# thermocouple_reader.net
KiCad netlist of a schematic drawn in EAGLE
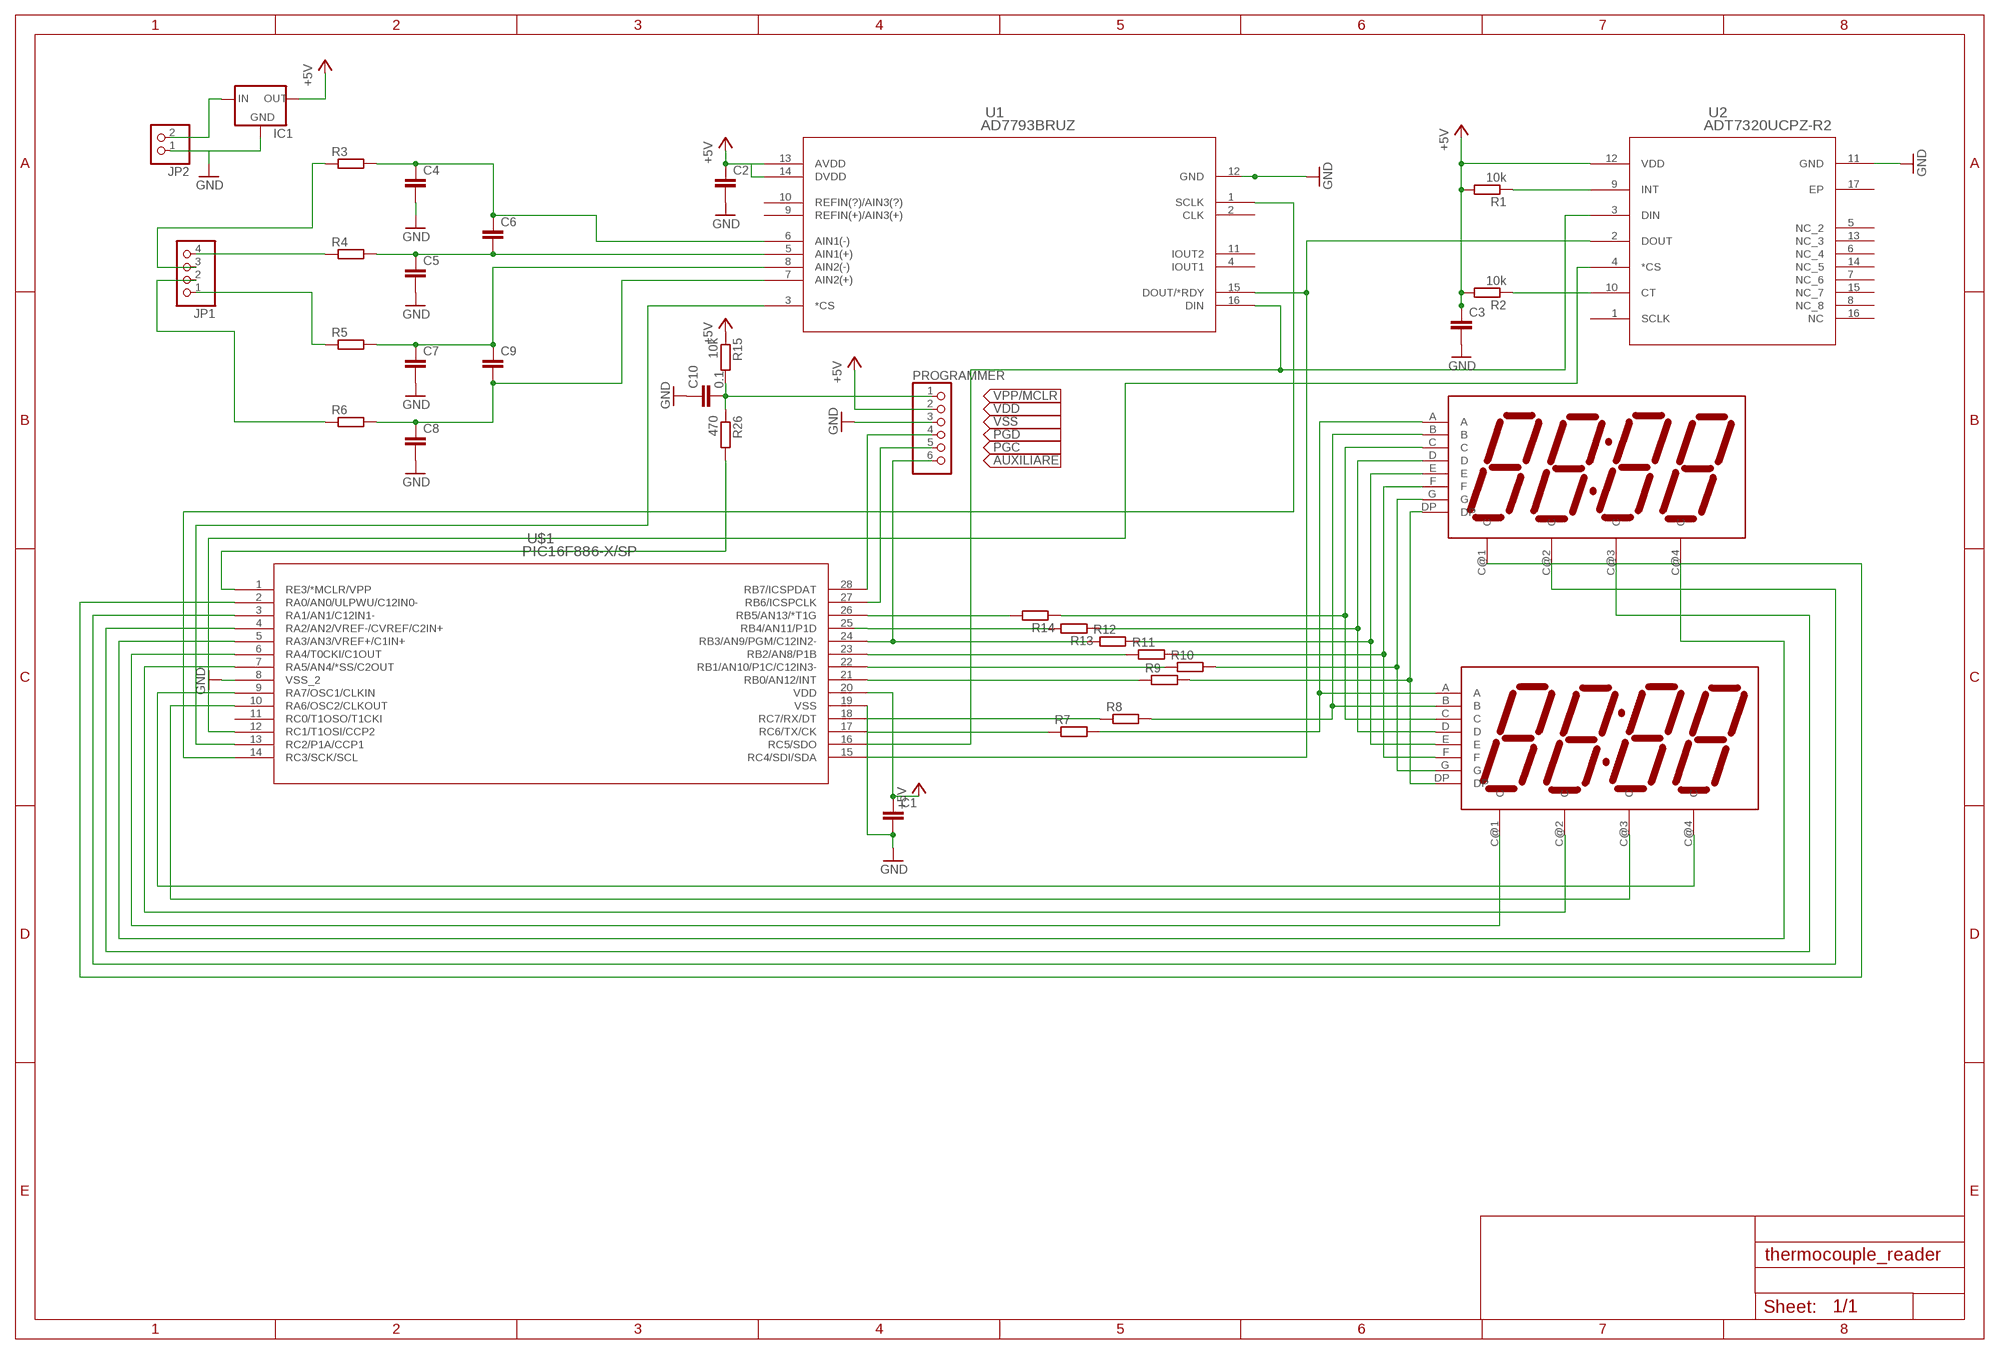
[diagram p0: schematic, sheet 1]

(export (version "E")
  (design (tool "Eeschema 10.0.6"))
  (components
    (comp (ref "C1")
      (value "C-EU025-024X044")
      (footprint "eagle-import:C025-024X044")
      (libsource (lib "eagle-import") (part "C-EU025-024X044"))
    )
    (comp (ref "C2")
      (value "C-EU025-024X044")
      (footprint "eagle-import:C025-024X044")
      (libsource (lib "eagle-import") (part "C-EU025-024X044"))
    )
    (comp (ref "C3")
      (value "C-EU025-024X044")
      (footprint "eagle-import:C025-024X044")
      (libsource (lib "eagle-import") (part "C-EU025-024X044"))
    )
    (comp (ref "C4")
      (value "C-EU025-025X050")
      (footprint "eagle-import:C025-025X050")
      (libsource (lib "eagle-import") (part "C-EU025-025X050"))
    )
    (comp (ref "C5")
      (value "C-EU025-025X050")
      (footprint "eagle-import:C025-025X050")
      (libsource (lib "eagle-import") (part "C-EU025-025X050"))
    )
    (comp (ref "C6")
      (value "C-EU025-024X044")
      (footprint "eagle-import:C025-024X044")
      (libsource (lib "eagle-import") (part "C-EU025-024X044"))
    )
    (comp (ref "C7")
      (value "C-EU025-025X050")
      (footprint "eagle-import:C025-025X050")
      (libsource (lib "eagle-import") (part "C-EU025-025X050"))
    )
    (comp (ref "C8")
      (value "C-EU025-025X050")
      (footprint "eagle-import:C025-025X050")
      (libsource (lib "eagle-import") (part "C-EU025-025X050"))
    )
    (comp (ref "C9")
      (value "C-EU025-024X044")
      (footprint "eagle-import:C025-024X044")
      (libsource (lib "eagle-import") (part "C-EU025-024X044"))
    )
    (comp (ref "C10")
      (value "0.1")
      (footprint "eagle-import:C025-025X050")
      (libsource (lib "eagle-import") (part "C-EU025-025X050"))
    )
    (comp (ref "IC1")
      (value "78LXX")
      (footprint "eagle-import:78LXX")
      (libsource (lib "eagle-import") (part "78LXX"))
    )
    (comp (ref "JP1")
      (value "PINHD-1X4")
      (footprint "eagle-import:1X04")
      (libsource (lib "eagle-import") (part "PINHD-1X4"))
    )
    (comp (ref "JP2")
      (value "PINHD-1X2")
      (footprint "eagle-import:1X02")
      (libsource (lib "eagle-import") (part "PINHD-1X2"))
    )
    (comp (ref "PROGRAMMER")
      (value "PINHD-1X6")
      (footprint "eagle-import:1X06")
      (libsource (lib "eagle-import") (part "PINHD-1X6"))
    )
    (comp (ref "R1")
      (value "10k")
      (footprint "eagle-import:0204_5")
      (libsource (lib "eagle-import") (part "R-EU_0204/5"))
    )
    (comp (ref "R2")
      (value "10k")
      (footprint "eagle-import:0204_5")
      (libsource (lib "eagle-import") (part "R-EU_0204/5"))
    )
    (comp (ref "R3")
      (value "R-EU_0204/5")
      (footprint "eagle-import:0204_5")
      (libsource (lib "eagle-import") (part "R-EU_0204/5"))
    )
    (comp (ref "R4")
      (value "R-EU_0204/5")
      (footprint "eagle-import:0204_5")
      (libsource (lib "eagle-import") (part "R-EU_0204/5"))
    )
    (comp (ref "R5")
      (value "R-EU_0204/5")
      (footprint "eagle-import:0204_5")
      (libsource (lib "eagle-import") (part "R-EU_0204/5"))
    )
    (comp (ref "R6")
      (value "R-EU_0204/5")
      (footprint "eagle-import:0204_5")
      (libsource (lib "eagle-import") (part "R-EU_0204/5"))
    )
    (comp (ref "R7")
      (value "R-EU_0207/10")
      (footprint "eagle-import:0207_10")
      (libsource (lib "eagle-import") (part "R-EU_0207/10"))
    )
    (comp (ref "R8")
      (value "R-EU_0207/15")
      (footprint "eagle-import:0207_15")
      (libsource (lib "eagle-import") (part "R-EU_0207/15"))
    )
    (comp (ref "R9")
      (value "R-EU_0207/15")
      (footprint "eagle-import:0207_15")
      (libsource (lib "eagle-import") (part "R-EU_0207/15"))
    )
    (comp (ref "R10")
      (value "R-EU_0207/15")
      (footprint "eagle-import:0207_15")
      (libsource (lib "eagle-import") (part "R-EU_0207/15"))
    )
    (comp (ref "R11")
      (value "R-EU_0207/15")
      (footprint "eagle-import:0207_15")
      (libsource (lib "eagle-import") (part "R-EU_0207/15"))
    )
    (comp (ref "R12")
      (value "R-EU_0204/5")
      (footprint "eagle-import:0204_5")
      (libsource (lib "eagle-import") (part "R-EU_0204/5"))
    )
    (comp (ref "R13")
      (value "R-EU_0204/5")
      (footprint "eagle-import:0204_5")
      (libsource (lib "eagle-import") (part "R-EU_0204/5"))
    )
    (comp (ref "R14")
      (value "R-EU_0207/15")
      (footprint "eagle-import:0207_15")
      (libsource (lib "eagle-import") (part "R-EU_0207/15"))
    )
    (comp (ref "R15")
      (value "10k")
      (footprint "eagle-import:0204_5")
      (libsource (lib "eagle-import") (part "R-EU_0204/5"))
    )
    (comp (ref "R26")
      (value "470")
      (footprint "eagle-import:0204_5")
      (libsource (lib "eagle-import") (part "R-EU_0204/5"))
    )
    (comp (ref "U$1")
      (value "PIC16F886-X/SP")
      (footprint "eagle-import:SPDIP28_300MC")
      (libsource (lib "eagle-import") (part "PIC16F886-X/SP"))
    )
    (comp (ref "U$2")
      (value "HDSP-BO1E")
      (footprint "eagle-import:HDSP-B01")
      (libsource (lib "eagle-import") (part "HDSP-BO1E"))
    )
    (comp (ref "U$3")
      (value "HDSP-BO1E")
      (footprint "eagle-import:HDSP-B01")
      (libsource (lib "eagle-import") (part "HDSP-BO1E"))
    )
    (comp (ref "U1")
      (value "AD7793BRUZ")
      (footprint "eagle-import:RU_16")
      (libsource (lib "eagle-import") (part "AD7793BRUZ"))
    )
    (comp (ref "U2")
      (value "ADT7320UCPZ-R2")
      (footprint "eagle-import:CP_16_17")
      (libsource (lib "eagle-import") (part "ADT7320UCPZ-R2"))
    )
  )
  (nets
    (net (code "1") (name "+5V") (class "Default")
      (node (ref "C1") (pin "1") (pinfunction "1_1") (pintype "passive"))
      (node (ref "C2") (pin "1") (pinfunction "1_1") (pintype "passive"))
      (node (ref "C3") (pin "1") (pinfunction "1_1") (pintype "passive"))
      (node (ref "IC1") (pin "OUT") (pinfunction "OUT_OUT") (pintype "passive"))
      (node (ref "PROGRAMMER") (pin "2") (pinfunction "2_2") (pintype "passive"))
      (node (ref "R1") (pin "2") (pinfunction "2_2") (pintype "passive"))
      (node (ref "R15") (pin "1") (pinfunction "1_1") (pintype "passive"))
      (node (ref "R2") (pin "2") (pinfunction "2_2") (pintype "passive"))
      (node (ref "U$1") (pin "20") (pinfunction "VDD_20") (pintype "passive"))
      (node (ref "U1") (pin "13") (pinfunction "AVDD_13") (pintype "power_in"))
      (node (ref "U1") (pin "14") (pinfunction "DVDD_14") (pintype "power_in"))
      (node (ref "U2") (pin "12") (pinfunction "VDD_12") (pintype "passive"))
    )
    (net (code "2") (name "GND") (class "Default")
      (node (ref "C1") (pin "2") (pinfunction "2_2") (pintype "passive"))
      (node (ref "C10") (pin "1") (pinfunction "1_1") (pintype "passive"))
      (node (ref "C2") (pin "2") (pinfunction "2_2") (pintype "passive"))
      (node (ref "C3") (pin "2") (pinfunction "2_2") (pintype "passive"))
      (node (ref "C4") (pin "2") (pinfunction "2_2") (pintype "passive"))
      (node (ref "C5") (pin "2") (pinfunction "2_2") (pintype "passive"))
      (node (ref "C7") (pin "2") (pinfunction "2_2") (pintype "passive"))
      (node (ref "C8") (pin "2") (pinfunction "2_2") (pintype "passive"))
      (node (ref "IC1") (pin "GND") (pinfunction "GND_GND") (pintype "input"))
      (node (ref "JP2") (pin "1") (pinfunction "1_1") (pintype "passive"))
      (node (ref "PROGRAMMER") (pin "3") (pinfunction "3_3") (pintype "passive"))
      (node (ref "U$1") (pin "19") (pinfunction "VSS_19") (pintype "passive"))
      (node (ref "U$1") (pin "8") (pinfunction "VSS_2_8") (pintype "passive"))
      (node (ref "U1") (pin "12") (pinfunction "GND_12") (pintype "passive"))
      (node (ref "U2") (pin "11") (pinfunction "GND_11") (pintype "passive"))
    )
    (net (code "3") (name "Net-(C10-Pad2)") (class "Default")
      (node (ref "C10") (pin "2") (pinfunction "2_2") (pintype "passive"))
      (node (ref "PROGRAMMER") (pin "1") (pinfunction "1_1") (pintype "passive"))
      (node (ref "R15") (pin "2") (pinfunction "2_2") (pintype "passive"))
      (node (ref "R26") (pin "1") (pinfunction "1_1") (pintype "passive"))
    )
    (net (code "4") (name "Net-(IC1-PadIN)") (class "Default")
      (node (ref "IC1") (pin "IN") (pinfunction "IN_IN") (pintype "input"))
      (node (ref "JP2") (pin "2") (pinfunction "2_2") (pintype "passive"))
    )
    (net (code "5") (name "Net-(JP1-Pad1)") (class "Default")
      (node (ref "JP1") (pin "1") (pinfunction "1_1") (pintype "passive"))
      (node (ref "R5") (pin "1") (pinfunction "1_1") (pintype "passive"))
    )
    (net (code "6") (name "Net-(JP1-Pad2)") (class "Default")
      (node (ref "JP1") (pin "2") (pinfunction "2_2") (pintype "passive"))
      (node (ref "R6") (pin "1") (pinfunction "1_1") (pintype "passive"))
    )
    (net (code "7") (name "Net-(JP1-Pad3)") (class "Default")
      (node (ref "JP1") (pin "3") (pinfunction "3_3") (pintype "passive"))
      (node (ref "R3") (pin "1") (pinfunction "1_1") (pintype "passive"))
    )
    (net (code "8") (name "Net-(JP1-Pad4)") (class "Default")
      (node (ref "JP1") (pin "4") (pinfunction "4_4") (pintype "passive"))
      (node (ref "R4") (pin "1") (pinfunction "1_1") (pintype "passive"))
    )
    (net (code "9") (name "Net-(R7-Pad2)") (class "Default")
      (node (ref "R7") (pin "2") (pinfunction "2_2") (pintype "passive"))
      (node (ref "U$2") (pin "A") (pinfunction "A_A") (pintype "passive"))
      (node (ref "U$3") (pin "A") (pinfunction "A_A") (pintype "passive"))
    )
    (net (code "10") (name "Net-(R8-Pad2)") (class "Default")
      (node (ref "R8") (pin "2") (pinfunction "2_2") (pintype "passive"))
      (node (ref "U$2") (pin "B") (pinfunction "B_B") (pintype "passive"))
      (node (ref "U$3") (pin "B") (pinfunction "B_B") (pintype "passive"))
    )
    (net (code "11") (name "Net-(R9-Pad2)") (class "Default")
      (node (ref "R9") (pin "2") (pinfunction "2_2") (pintype "passive"))
      (node (ref "U$2") (pin "DP") (pinfunction "DP_DP") (pintype "passive"))
      (node (ref "U$3") (pin "DP") (pinfunction "DP_DP") (pintype "passive"))
    )
    (net (code "12") (name "Net-(R10-Pad2)") (class "Default")
      (node (ref "R10") (pin "2") (pinfunction "2_2") (pintype "passive"))
      (node (ref "U$2") (pin "G") (pinfunction "G_G") (pintype "passive"))
      (node (ref "U$3") (pin "G") (pinfunction "G_G") (pintype "passive"))
    )
    (net (code "13") (name "Net-(R11-Pad2)") (class "Default")
      (node (ref "R11") (pin "2") (pinfunction "2_2") (pintype "passive"))
      (node (ref "U$2") (pin "F") (pinfunction "F_F") (pintype "passive"))
      (node (ref "U$3") (pin "F") (pinfunction "F_F") (pintype "passive"))
    )
    (net (code "14") (name "Net-(R12-Pad2)") (class "Default")
      (node (ref "R12") (pin "2") (pinfunction "2_2") (pintype "passive"))
      (node (ref "U$2") (pin "E") (pinfunction "E_E") (pintype "passive"))
      (node (ref "U$3") (pin "E") (pinfunction "E_E") (pintype "passive"))
    )
    (net (code "15") (name "Net-(R13-Pad1)") (class "Default")
      (node (ref "R13") (pin "1") (pinfunction "1_1") (pintype "passive"))
      (node (ref "U$2") (pin "D") (pinfunction "D_D") (pintype "passive"))
      (node (ref "U$3") (pin "D") (pinfunction "D_D") (pintype "passive"))
    )
    (net (code "16") (name "Net-(R14-Pad1)") (class "Default")
      (node (ref "R14") (pin "1") (pinfunction "1_1") (pintype "passive"))
      (node (ref "U$2") (pin "C") (pinfunction "C_C") (pintype "passive"))
      (node (ref "U$3") (pin "C") (pinfunction "C_C") (pintype "passive"))
    )
    (net (code "17") (name "Net-(U$1-RA0{slash}AN0{slash}ULPWU{slash}C12IN0-)") (class "Default")
      (node (ref "U$1") (pin "2") (pinfunction "RA0/AN0/ULPWU/C12IN0-_2") (pintype "passive"))
      (node (ref "U$2") (pin "C@1") (pinfunction "C_C@1") (pintype "passive"))
    )
    (net (code "18") (name "Net-(U$1-RA1{slash}AN1{slash}C12IN1-)") (class "Default")
      (node (ref "U$1") (pin "3") (pinfunction "RA1/AN1/C12IN1-_3") (pintype "passive"))
      (node (ref "U$2") (pin "C@2") (pinfunction "C_C@2") (pintype "passive"))
    )
    (net (code "19") (name "Net-(U$1-RA2{slash}AN2{slash}VREF-{slash}CVREF{slash}C2IN+)") (class "Default")
      (node (ref "U$1") (pin "4") (pinfunction "RA2/AN2/VREF-/CVREF/C2IN+_4") (pintype "passive"))
      (node (ref "U$2") (pin "C@3") (pinfunction "C_C@3") (pintype "passive"))
    )
    (net (code "20") (name "Net-(U$1-RA3{slash}AN3{slash}VREF+{slash}C1IN+)") (class "Default")
      (node (ref "U$1") (pin "5") (pinfunction "RA3/AN3/VREF+/C1IN+_5") (pintype "passive"))
      (node (ref "U$2") (pin "C@4") (pinfunction "C_C@4") (pintype "passive"))
    )
    (net (code "21") (name "Net-(U$1-RA4{slash}T0CKI{slash}C1OUT)") (class "Default")
      (node (ref "U$1") (pin "6") (pinfunction "RA4/T0CKI/C1OUT_6") (pintype "passive"))
      (node (ref "U$3") (pin "C@1") (pinfunction "C_C@1") (pintype "passive"))
    )
    (net (code "22") (name "Net-(U$1-RA5{slash}AN4{slash}*SS{slash}C2OUT)") (class "Default")
      (node (ref "U$1") (pin "7") (pinfunction "RA5/AN4/*SS/C2OUT_7") (pintype "passive"))
      (node (ref "U$3") (pin "C@2") (pinfunction "C_C@2") (pintype "passive"))
    )
    (net (code "23") (name "Net-(U$1-RA6{slash}OSC2{slash}CLKOUT)") (class "Default")
      (node (ref "U$1") (pin "10") (pinfunction "RA6/OSC2/CLKOUT_10") (pintype "passive"))
      (node (ref "U$3") (pin "C@3") (pinfunction "C_C@3") (pintype "passive"))
    )
    (net (code "24") (name "Net-(U$1-RA7{slash}OSC1{slash}CLKIN)") (class "Default")
      (node (ref "U$1") (pin "9") (pinfunction "RA7/OSC1/CLKIN_9") (pintype "passive"))
      (node (ref "U$3") (pin "C@4") (pinfunction "C_C@4") (pintype "passive"))
    )
    (net (code "25") (name "Net-(U$1-RB0{slash}AN12{slash}INT)") (class "Default")
      (node (ref "R9") (pin "1") (pinfunction "1_1") (pintype "passive"))
      (node (ref "U$1") (pin "21") (pinfunction "RB0/AN12/INT_21") (pintype "passive"))
    )
    (net (code "26") (name "Net-(U$1-RB1{slash}AN10{slash}P1C{slash}C12IN3-)") (class "Default")
      (node (ref "R10") (pin "1") (pinfunction "1_1") (pintype "passive"))
      (node (ref "U$1") (pin "22") (pinfunction "RB1/AN10/P1C/C12IN3-_22") (pintype "passive"))
    )
    (net (code "27") (name "Net-(U$1-RB2{slash}AN8{slash}P1B)") (class "Default")
      (node (ref "R11") (pin "1") (pinfunction "1_1") (pintype "passive"))
      (node (ref "U$1") (pin "23") (pinfunction "RB2/AN8/P1B_23") (pintype "passive"))
    )
    (net (code "28") (name "Net-(U$1-RB3{slash}AN9{slash}PGM{slash}C12IN2-)") (class "Default")
      (node (ref "PROGRAMMER") (pin "6") (pinfunction "6_6") (pintype "passive"))
      (node (ref "R12") (pin "1") (pinfunction "1_1") (pintype "passive"))
      (node (ref "U$1") (pin "24") (pinfunction "RB3/AN9/PGM/C12IN2-_24") (pintype "passive"))
    )
    (net (code "29") (name "Net-(U$1-RB4{slash}AN11{slash}P1D)") (class "Default")
      (node (ref "R13") (pin "2") (pinfunction "2_2") (pintype "passive"))
      (node (ref "U$1") (pin "25") (pinfunction "RB4/AN11/P1D_25") (pintype "passive"))
    )
    (net (code "30") (name "Net-(U$1-RB5{slash}AN13{slash}*T1G)") (class "Default")
      (node (ref "R14") (pin "2") (pinfunction "2_2") (pintype "passive"))
      (node (ref "U$1") (pin "26") (pinfunction "RB5/AN13/*T1G_26") (pintype "passive"))
    )
    (net (code "31") (name "Net-(U$1-RB6{slash}ICSPCLK)") (class "Default")
      (node (ref "PROGRAMMER") (pin "5") (pinfunction "5_5") (pintype "passive"))
      (node (ref "U$1") (pin "27") (pinfunction "RB6/ICSPCLK_27") (pintype "passive"))
    )
    (net (code "32") (name "Net-(U$1-RB7{slash}ICSPDAT)") (class "Default")
      (node (ref "PROGRAMMER") (pin "4") (pinfunction "4_4") (pintype "passive"))
      (node (ref "U$1") (pin "28") (pinfunction "RB7/ICSPDAT_28") (pintype "passive"))
    )
    (net (code "33") (name "Net-(U$1-RC1{slash}T1OSI{slash}CCP2)") (class "Default")
      (node (ref "U$1") (pin "12") (pinfunction "RC1/T1OSI/CCP2_12") (pintype "passive"))
      (node (ref "U2") (pin "4") (pinfunction "*CS_4") (pintype "passive"))
    )
    (net (code "34") (name "Net-(U$1-RC2{slash}P1A{slash}CCP1)") (class "Default")
      (node (ref "U$1") (pin "13") (pinfunction "RC2/P1A/CCP1_13") (pintype "passive"))
      (node (ref "U1") (pin "3") (pinfunction "*CS_3") (pintype "input"))
    )
    (net (code "35") (name "Net-(U$1-RC3{slash}SCK{slash}SCL)") (class "Default")
      (node (ref "U$1") (pin "14") (pinfunction "RC3/SCK/SCL_14") (pintype "passive"))
      (node (ref "U1") (pin "1") (pinfunction "SCLK_1") (pintype "input"))
    )
    (net (code "36") (name "Net-(U$1-RC4{slash}SDI{slash}SDA)") (class "Default")
      (node (ref "U$1") (pin "15") (pinfunction "RC4/SDI/SDA_15") (pintype "passive"))
      (node (ref "U1") (pin "15") (pinfunction "DOUT/*RDY_15") (pintype "output"))
      (node (ref "U2") (pin "2") (pinfunction "DOUT_2") (pintype "passive"))
    )
    (net (code "37") (name "Net-(U$1-RC5{slash}SDO)") (class "Default")
      (node (ref "U$1") (pin "16") (pinfunction "RC5/SDO_16") (pintype "passive"))
      (node (ref "U1") (pin "16") (pinfunction "DIN_16") (pintype "input"))
      (node (ref "U2") (pin "3") (pinfunction "DIN_3") (pintype "passive"))
    )
    (net (code "38") (name "Net-(U$1-RC6{slash}TX{slash}CK)") (class "Default")
      (node (ref "R7") (pin "1") (pinfunction "1_1") (pintype "passive"))
      (node (ref "U$1") (pin "17") (pinfunction "RC6/TX/CK_17") (pintype "passive"))
    )
    (net (code "39") (name "Net-(U$1-RC7{slash}RX{slash}DT)") (class "Default")
      (node (ref "R8") (pin "1") (pinfunction "1_1") (pintype "passive"))
      (node (ref "U$1") (pin "18") (pinfunction "RC7/RX/DT_18") (pintype "passive"))
    )
    (net (code "40") (name "Net-(U$1-RE3{slash}*MCLR{slash}VPP)") (class "Default")
      (node (ref "R26") (pin "2") (pinfunction "2_2") (pintype "passive"))
      (node (ref "U$1") (pin "1") (pinfunction "RE3/*MCLR/VPP_1") (pintype "passive"))
    )
    (net (code "41") (name "Net-(U1-AIN1(+))") (class "Default")
      (node (ref "C5") (pin "1") (pinfunction "1_1") (pintype "passive"))
      (node (ref "C6") (pin "2") (pinfunction "2_2") (pintype "passive"))
      (node (ref "R4") (pin "2") (pinfunction "2_2") (pintype "passive"))
      (node (ref "U1") (pin "5") (pinfunction "AIN1(+)_5") (pintype "input"))
    )
    (net (code "42") (name "Net-(U1-AIN1(-))") (class "Default")
      (node (ref "C4") (pin "1") (pinfunction "1_1") (pintype "passive"))
      (node (ref "C6") (pin "1") (pinfunction "1_1") (pintype "passive"))
      (node (ref "R3") (pin "2") (pinfunction "2_2") (pintype "passive"))
      (node (ref "U1") (pin "6") (pinfunction "AIN1(-)_6") (pintype "input"))
    )
    (net (code "43") (name "Net-(U1-AIN2(+))") (class "Default")
      (node (ref "C8") (pin "1") (pinfunction "1_1") (pintype "passive"))
      (node (ref "C9") (pin "2") (pinfunction "2_2") (pintype "passive"))
      (node (ref "R6") (pin "2") (pinfunction "2_2") (pintype "passive"))
      (node (ref "U1") (pin "7") (pinfunction "AIN2(+)_7") (pintype "input"))
    )
    (net (code "44") (name "Net-(U1-AIN2(-))") (class "Default")
      (node (ref "C7") (pin "1") (pinfunction "1_1") (pintype "passive"))
      (node (ref "C9") (pin "1") (pinfunction "1_1") (pintype "passive"))
      (node (ref "R5") (pin "2") (pinfunction "2_2") (pintype "passive"))
      (node (ref "U1") (pin "8") (pinfunction "AIN2(-)_8") (pintype "input"))
    )
    (net (code "45") (name "Net-(U2-CT)") (class "Default")
      (node (ref "R2") (pin "1") (pinfunction "1_1") (pintype "passive"))
      (node (ref "U2") (pin "10") (pinfunction "CT_10") (pintype "passive"))
    )
    (net (code "46") (name "Net-(U2-INT)") (class "Default")
      (node (ref "R1") (pin "1") (pinfunction "1_1") (pintype "passive"))
      (node (ref "U2") (pin "9") (pinfunction "INT_9") (pintype "passive"))
    )
    (net (code "47") (name "unconnected-(U$1-RC0{slash}T1OSO{slash}T1CKI-Pad11)") (class "Default")
      (node (ref "U$1") (pin "11") (pinfunction "RC0/T1OSO/T1CKI_11") (pintype "passive"))
    )
    (net (code "48") (name "unconnected-(U1-CLK-Pad2)") (class "Default")
      (node (ref "U1") (pin "2") (pinfunction "CLK_2") (pintype "passive"))
    )
    (net (code "49") (name "unconnected-(U1-IOUT1-Pad4)") (class "Default")
      (node (ref "U1") (pin "4") (pinfunction "IOUT1_4") (pintype "output"))
    )
    (net (code "50") (name "unconnected-(U1-IOUT2-Pad11)") (class "Default")
      (node (ref "U1") (pin "11") (pinfunction "IOUT2_11") (pintype "output"))
    )
    (net (code "51") (name "unconnected-(U1-REFIN(+){slash}AIN3(+)-Pad9)") (class "Default")
      (node (ref "U1") (pin "9") (pinfunction "REFIN(+)/AIN3(+)_9") (pintype "input"))
    )
    (net (code "52") (name "unconnected-(U1-REFIN(?){slash}AIN3(?)-Pad10)") (class "Default")
      (node (ref "U1") (pin "10") (pinfunction "REFIN(?)/AIN3(?)_10") (pintype "input"))
    )
    (net (code "53") (name "unconnected-(U2-EP-Pad17)") (class "Default")
      (node (ref "U2") (pin "17") (pinfunction "EP_17") (pintype "passive"))
    )
    (net (code "54") (name "unconnected-(U2-NC-Pad16)") (class "Default")
      (node (ref "U2") (pin "16") (pinfunction "NC_16") (pintype "passive"))
    )
    (net (code "55") (name "unconnected-(U2-NC_2-Pad5)") (class "Default")
      (node (ref "U2") (pin "5") (pinfunction "NC_2_5") (pintype "passive"))
    )
    (net (code "56") (name "unconnected-(U2-NC_3-Pad13)") (class "Default")
      (node (ref "U2") (pin "13") (pinfunction "NC_3_13") (pintype "passive"))
    )
    (net (code "57") (name "unconnected-(U2-NC_4-Pad6)") (class "Default")
      (node (ref "U2") (pin "6") (pinfunction "NC_4_6") (pintype "passive"))
    )
    (net (code "58") (name "unconnected-(U2-NC_5-Pad14)") (class "Default")
      (node (ref "U2") (pin "14") (pinfunction "NC_5_14") (pintype "passive"))
    )
    (net (code "59") (name "unconnected-(U2-NC_6-Pad7)") (class "Default")
      (node (ref "U2") (pin "7") (pinfunction "NC_6_7") (pintype "passive"))
    )
    (net (code "60") (name "unconnected-(U2-NC_7-Pad15)") (class "Default")
      (node (ref "U2") (pin "15") (pinfunction "NC_7_15") (pintype "passive"))
    )
    (net (code "61") (name "unconnected-(U2-NC_8-Pad8)") (class "Default")
      (node (ref "U2") (pin "8") (pinfunction "NC_8_8") (pintype "passive"))
    )
    (net (code "62") (name "unconnected-(U2-SCLK-Pad1)") (class "Default")
      (node (ref "U2") (pin "1") (pinfunction "SCLK_1") (pintype "passive"))
    )
  )
)
